# X13-Backplane.net
KiCad netlist of a schematic drawn in EAGLE
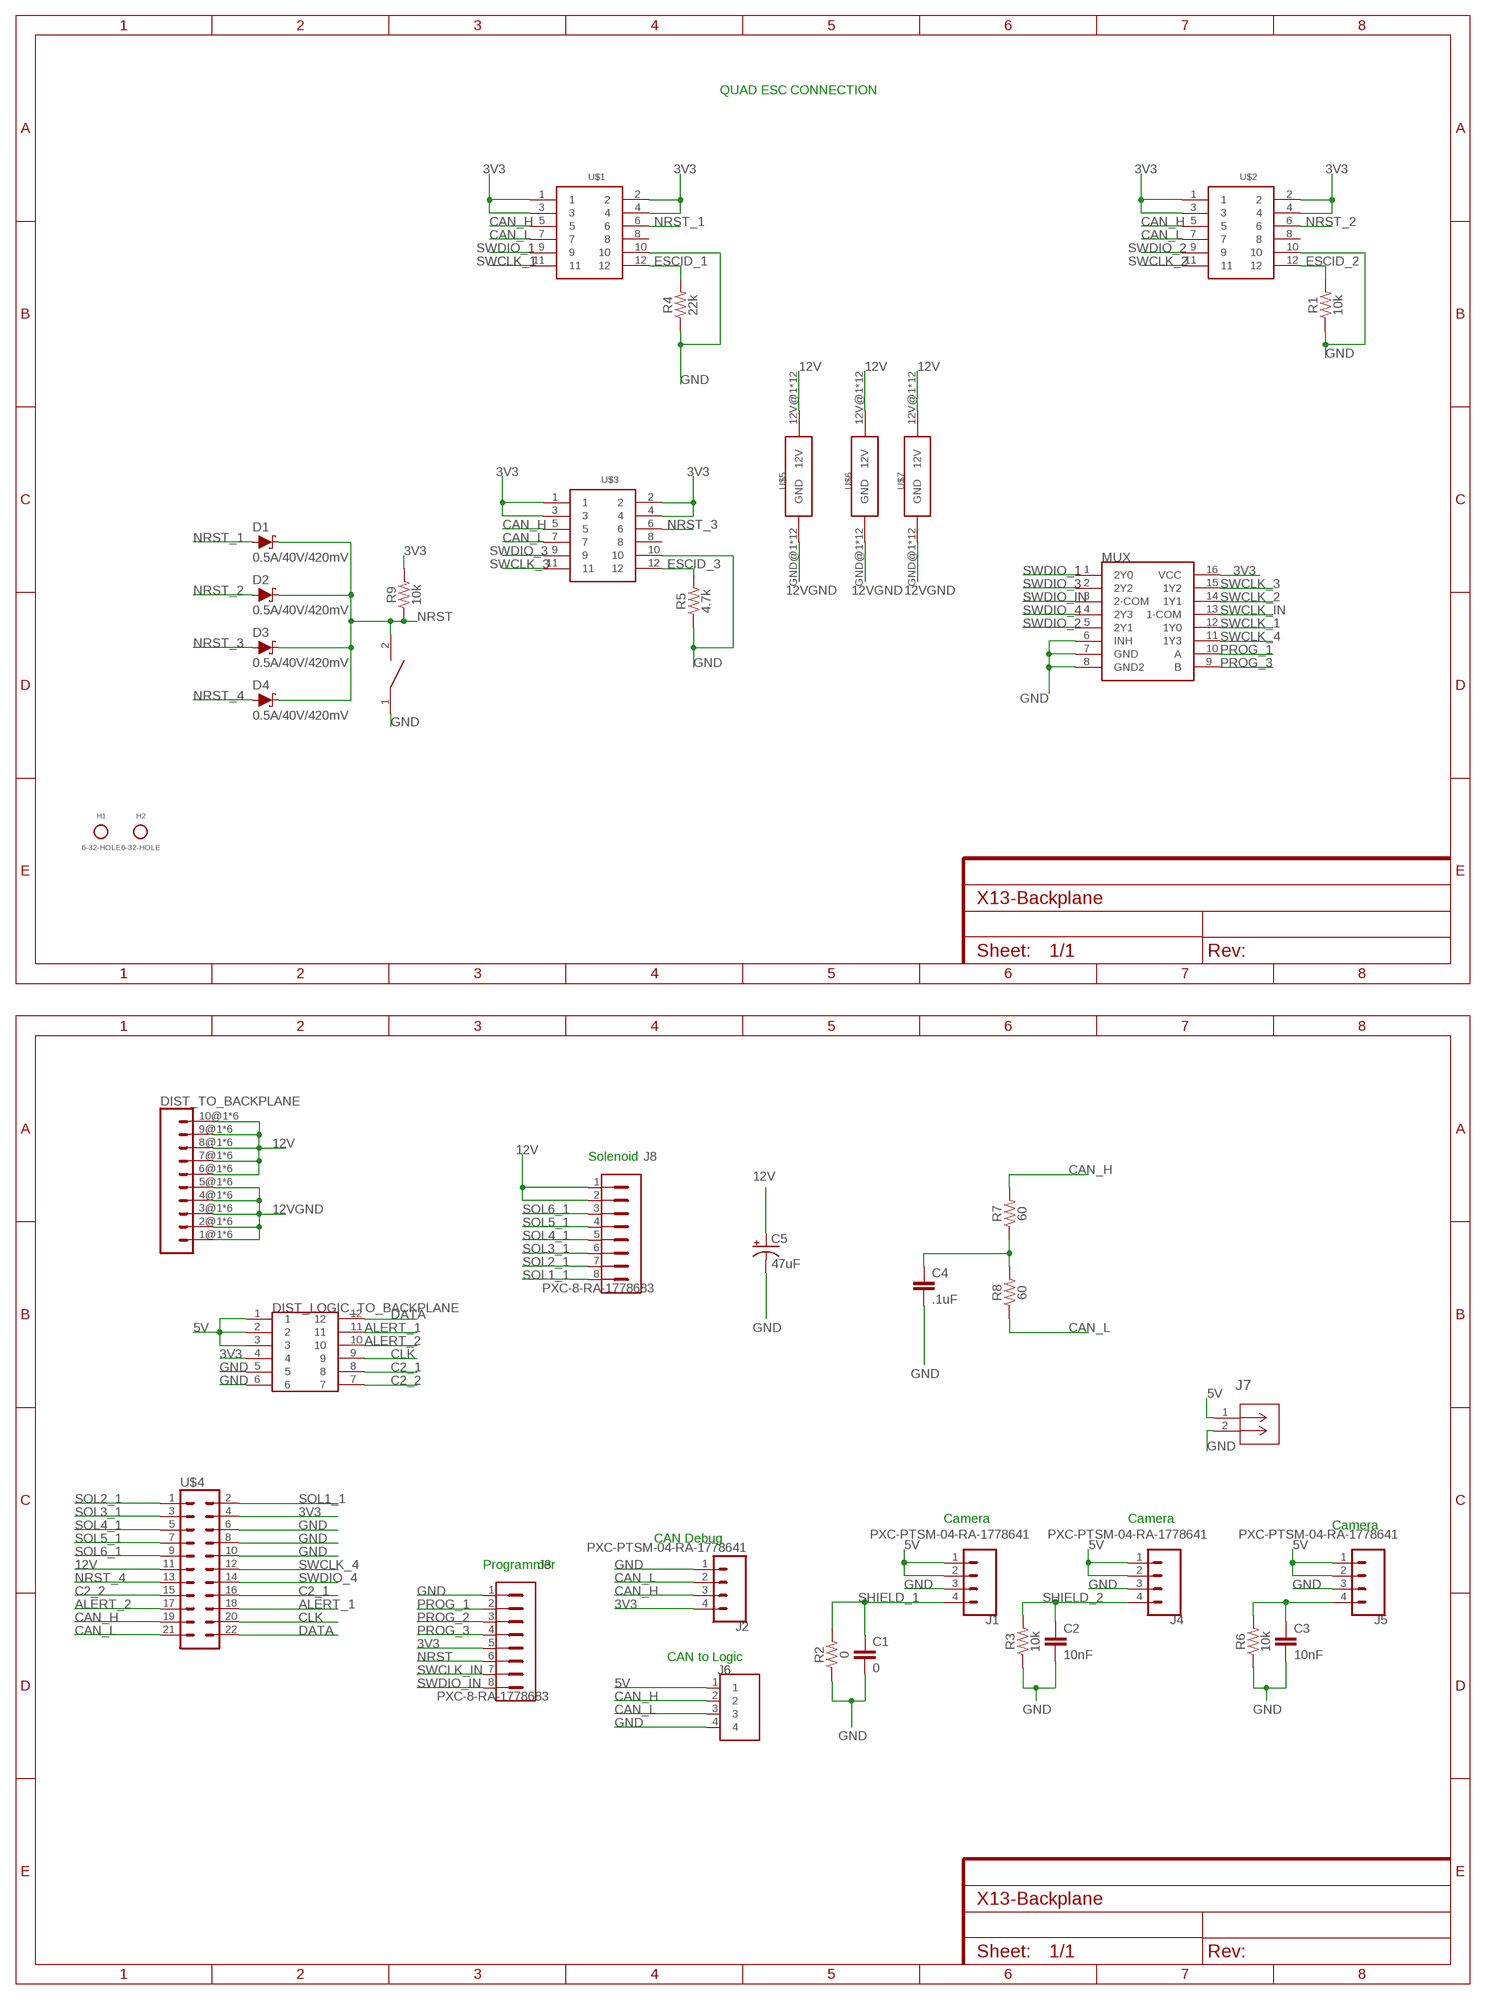
[diagram p0: schematic, sheet 1]

(export (version "E")
  (design (tool "Eeschema 10.0.6"))
  (components
    (comp (ref "C1")
      (value "0")
      (footprint "eagle-import:0603")
      (libsource (lib "eagle-import") (part "10NF-0603-50V-10%"))
    )
    (comp (ref "C2")
      (value "10nF")
      (footprint "eagle-import:0603")
      (libsource (lib "eagle-import") (part "10NF-0603-50V-10%"))
    )
    (comp (ref "C3")
      (value "10nF")
      (footprint "eagle-import:0603")
      (libsource (lib "eagle-import") (part "10NF-0603-50V-10%"))
    )
    (comp (ref "C4")
      (value ".1uF")
      (footprint "eagle-import:0603")
      (libsource (lib "eagle-import") (part "10NF-0603-50V-10%"))
    )
    (comp (ref "C5")
      (value "47uF")
      (footprint "eagle-import:PANASONIC_D")
      (libsource (lib "eagle-import") (part "47UF-POLAR-PANASONIC_D-35V-20%"))
    )
    (comp (ref "D1")
      (value "0.5A/40V/420mV")
      (footprint "eagle-import:SOD-323")
      (libsource (lib "eagle-import") (part "DIODE-SCHOTTKY-PMEG4005EJ"))
    )
    (comp (ref "D2")
      (value "0.5A/40V/420mV")
      (footprint "eagle-import:SOD-323")
      (libsource (lib "eagle-import") (part "DIODE-SCHOTTKY-PMEG4005EJ"))
    )
    (comp (ref "D3")
      (value "0.5A/40V/420mV")
      (footprint "eagle-import:SOD-323")
      (libsource (lib "eagle-import") (part "DIODE-SCHOTTKY-PMEG4005EJ"))
    )
    (comp (ref "D4")
      (value "0.5A/40V/420mV")
      (footprint "eagle-import:SOD-323")
      (libsource (lib "eagle-import") (part "DIODE-SCHOTTKY-PMEG4005EJ"))
    )
    (comp (ref "DIST_LOGIC_TO_BACKPLANE")
      (value "IPL1-106-01-L-D-K")
      (footprint "eagle-import:IPL1-106-01-L-D-K")
      (libsource (lib "eagle-import") (part "IPL1-106-01-L-D-K"))
    )
    (comp (ref "DIST_TO_BACKPLANE")
      (value "MPPT-10-01-01-L-RA-SD")
      (footprint "eagle-import:MPPT-10-01-01-L-RA-SD")
      (libsource (lib "eagle-import") (part "MPPT-10-01-01-L-RA-SD"))
    )
    (comp (ref "H1")
      (value "6-32-HOLE")
      (footprint "eagle-import:6-32-HOLE")
      (libsource (lib "eagle-import") (part "6-32-HOLE"))
    )
    (comp (ref "H2")
      (value "6-32-HOLE")
      (footprint "eagle-import:6-32-HOLE")
      (libsource (lib "eagle-import") (part "6-32-HOLE"))
    )
    (comp (ref "J1")
      (value "PXC-PTSM-04-RA-1778641")
      (footprint "eagle-import:PXC-PTSM-04-RA-1778641")
      (libsource (lib "eagle-import") (part "PXC-PTSM-04-RA-1778641"))
    )
    (comp (ref "J2")
      (value "PXC-PTSM-04-RA-1778641")
      (footprint "eagle-import:PXC-PTSM-04-RA-1778641")
      (libsource (lib "eagle-import") (part "PXC-PTSM-04-RA-1778641"))
    )
    (comp (ref "J3")
      (value "PXC-8-RA-1778683")
      (footprint "eagle-import:PXC-8-RA-1778683")
      (libsource (lib "eagle-import") (part "PXC-8-RA-1778683"))
    )
    (comp (ref "J4")
      (value "PXC-PTSM-04-RA-1778641")
      (footprint "eagle-import:PXC-PTSM-04-RA-1778641")
      (libsource (lib "eagle-import") (part "PXC-PTSM-04-RA-1778641"))
    )
    (comp (ref "J5")
      (value "PXC-PTSM-04-RA-1778641")
      (footprint "eagle-import:PXC-PTSM-04-RA-1778641")
      (libsource (lib "eagle-import") (part "PXC-PTSM-04-RA-1778641"))
    )
    (comp (ref "J6")
      (value "284512-4")
      (footprint "eagle-import:TE_284512-4")
      (fields (field (name "MANUFACTURER") "TE"))
      (libsource (lib "eagle-import") (part "284512-4"))
    )
    (comp (ref "J7")
      (value "POE_TERMINAL")
      (footprint "eagle-import:CONN2_282834-2_TEC")
      (fields
        (field (name "MANUFACTURER_PART_NUMBER") "282834-2")
        (field (name "COPYRIGHT") "Copyright (C) 2016 Accelerated Designs. All rights reserved")
      )
      (libsource (lib "eagle-import") (part "POE_TERMINAL"))
    )
    (comp (ref "J8")
      (value "PXC-8-RA-1778683")
      (footprint "eagle-import:PXC-8-RA-1778683")
      (libsource (lib "eagle-import") (part "PXC-8-RA-1778683"))
    )
    (comp (ref "MUX")
      (value "TI-SN74LV4052A")
      (footprint "eagle-import:SOIC-16")
      (libsource (lib "eagle-import") (part "TI-SN74LV4052A"))
    )
    (comp (ref "R1")
      (value "10k")
      (footprint "eagle-import:0603")
      (libsource (lib "eagle-import") (part "10KOHM-0603-1/10W-1%"))
    )
    (comp (ref "R2")
      (value "0")
      (footprint "eagle-import:0603")
      (libsource (lib "eagle-import") (part "10KOHM-0603-1/10W-1%"))
    )
    (comp (ref "R3")
      (value "10k")
      (footprint "eagle-import:0603")
      (libsource (lib "eagle-import") (part "10KOHM-0603-1/10W-1%"))
    )
    (comp (ref "R4")
      (value "22k")
      (footprint "eagle-import:0603")
      (libsource (lib "eagle-import") (part "26.7KOHM0603-1/10W-1%"))
    )
    (comp (ref "R5")
      (value "4.7k")
      (footprint "eagle-import:0603")
      (libsource (lib "eagle-import") (part "1KOHM-0603-1/10W-1%"))
    )
    (comp (ref "R6")
      (value "10k")
      (footprint "eagle-import:0603")
      (libsource (lib "eagle-import") (part "10KOHM-0603-1/10W-1%"))
    )
    (comp (ref "R7")
      (value "60")
      (footprint "eagle-import:0603")
      (libsource (lib "eagle-import") (part "68.1KOHM-0603-1/10W-1%"))
    )
    (comp (ref "R8")
      (value "60")
      (footprint "eagle-import:0603")
      (libsource (lib "eagle-import") (part "68.1KOHM-0603-1/10W-1%"))
    )
    (comp (ref "R9")
      (value "10k")
      (footprint "eagle-import:0603")
      (libsource (lib "eagle-import") (part "10KOHM-0603-1/10W-1%"))
    )
    (comp (ref "U$1")
      (value "BACKPLANE_CONNECTORSBKP")
      (footprint "eagle-import:BACKPLANE_CONNECTORS_BKP")
      (libsource (lib "eagle-import") (part "BACKPLANE_CONNECTORSBKP"))
    )
    (comp (ref "U$2")
      (value "BACKPLANE_CONNECTORSBKP")
      (footprint "eagle-import:BACKPLANE_CONNECTORS_BKP")
      (libsource (lib "eagle-import") (part "BACKPLANE_CONNECTORSBKP"))
    )
    (comp (ref "U$3")
      (value "BACKPLANE_CONNECTORSBKP")
      (footprint "eagle-import:BACKPLANE_CONNECTORS_BKP")
      (libsource (lib "eagle-import") (part "BACKPLANE_CONNECTORSBKP"))
    )
    (comp (ref "U$4")
      (value "BKP-TO-SOL")
      (footprint "eagle-import:BKP-TO-SOL_TMM-111-01-T-D")
      (libsource (lib "eagle-import") (part "BKP-TO-SOL"))
    )
    (comp (ref "U$5")
      (value "BACKPLANE_ESC_ADAPTER_PWRBKP")
      (footprint "eagle-import:BACKPLANE_ESC_ADAPTER_BKP_PWR")
      (libsource (lib "eagle-import") (part "BACKPLANE_ESC_ADAPTER_PWRBKP"))
    )
    (comp (ref "U$6")
      (value "BACKPLANE_ESC_ADAPTER_PWRBKP")
      (footprint "eagle-import:BACKPLANE_ESC_ADAPTER_BKP_PWR")
      (libsource (lib "eagle-import") (part "BACKPLANE_ESC_ADAPTER_PWRBKP"))
    )
    (comp (ref "U$7")
      (value "BACKPLANE_ESC_ADAPTER_PWRBKP")
      (footprint "eagle-import:BACKPLANE_ESC_ADAPTER_BKP_PWR")
      (libsource (lib "eagle-import") (part "BACKPLANE_ESC_ADAPTER_PWRBKP"))
    )
    (comp (ref "U$8")
      (value "DISCRETECOMPONENTS_SWITCH")
      (footprint "eagle-import:DISCRETECOMPONENTS_SW_2512")
      (libsource (lib "eagle-import") (part "DISCRETECOMPONENTS_SWITCH"))
    )
  )
  (nets
    (net (code "1") (name "/3V3") (class "Default")
      (node (ref "DIST_LOGIC_TO_BACKPLANE") (pin "4") (pinfunction "4_4") (pintype "bidirectional"))
      (node (ref "J2") (pin "4") (pinfunction "4_4") (pintype "passive"))
      (node (ref "J3") (pin "5") (pinfunction "5_5") (pintype "passive"))
      (node (ref "MUX") (pin "16") (pinfunction "VCC_16") (pintype "bidirectional"))
      (node (ref "R9") (pin "2") (pinfunction "2_2") (pintype "passive"))
      (node (ref "U$1") (pin "1") (pinfunction "1_1") (pintype "passive"))
      (node (ref "U$1") (pin "2") (pinfunction "2_2") (pintype "passive"))
      (node (ref "U$1") (pin "3") (pinfunction "3_3") (pintype "passive"))
      (node (ref "U$1") (pin "4") (pinfunction "4_4") (pintype "passive"))
      (node (ref "U$2") (pin "1") (pinfunction "1_1") (pintype "passive"))
      (node (ref "U$2") (pin "2") (pinfunction "2_2") (pintype "passive"))
      (node (ref "U$2") (pin "3") (pinfunction "3_3") (pintype "passive"))
      (node (ref "U$2") (pin "4") (pinfunction "4_4") (pintype "passive"))
      (node (ref "U$3") (pin "1") (pinfunction "1_1") (pintype "passive"))
      (node (ref "U$3") (pin "2") (pinfunction "2_2") (pintype "passive"))
      (node (ref "U$3") (pin "3") (pinfunction "3_3") (pintype "passive"))
      (node (ref "U$3") (pin "4") (pinfunction "4_4") (pintype "passive"))
      (node (ref "U$4") (pin "4") (pinfunction "4_4") (pintype "passive"))
    )
    (net (code "2") (name "/5V") (class "Default")
      (node (ref "DIST_LOGIC_TO_BACKPLANE") (pin "1") (pinfunction "1_1") (pintype "bidirectional"))
      (node (ref "DIST_LOGIC_TO_BACKPLANE") (pin "2") (pinfunction "2_2") (pintype "bidirectional"))
      (node (ref "DIST_LOGIC_TO_BACKPLANE") (pin "3") (pinfunction "3_3") (pintype "bidirectional"))
      (node (ref "J1") (pin "1") (pinfunction "1_1") (pintype "passive"))
      (node (ref "J1") (pin "2") (pinfunction "2_2") (pintype "passive"))
      (node (ref "J4") (pin "1") (pinfunction "1_1") (pintype "passive"))
      (node (ref "J4") (pin "2") (pinfunction "2_2") (pintype "passive"))
      (node (ref "J5") (pin "1") (pinfunction "1_1") (pintype "passive"))
      (node (ref "J5") (pin "2") (pinfunction "2_2") (pintype "passive"))
      (node (ref "J6") (pin "1") (pinfunction "1_1") (pintype "passive"))
      (node (ref "J7") (pin "1") (pinfunction "1_1") (pintype "passive"))
    )
    (net (code "3") (name "/12V") (class "Default")
      (node (ref "C5") (pin "+") (pinfunction "+_+") (pintype "passive"))
      (node (ref "DIST_TO_BACKPLANE") (pin "10@1") (pinfunction "10_10@1") (pintype "passive"))
      (node (ref "DIST_TO_BACKPLANE") (pin "10@2") (pinfunction "10_10@2") (pintype "passive"))
      (node (ref "DIST_TO_BACKPLANE") (pin "10@3") (pinfunction "10_10@3") (pintype "passive"))
      (node (ref "DIST_TO_BACKPLANE") (pin "10@4") (pinfunction "10_10@4") (pintype "passive"))
      (node (ref "DIST_TO_BACKPLANE") (pin "10@5") (pinfunction "10_10@5") (pintype "passive"))
      (node (ref "DIST_TO_BACKPLANE") (pin "10@6") (pinfunction "10_10@6") (pintype "passive"))
      (node (ref "DIST_TO_BACKPLANE") (pin "6@1") (pinfunction "6_6@1") (pintype "passive"))
      (node (ref "DIST_TO_BACKPLANE") (pin "6@2") (pinfunction "6_6@2") (pintype "passive"))
      (node (ref "DIST_TO_BACKPLANE") (pin "6@3") (pinfunction "6_6@3") (pintype "passive"))
      (node (ref "DIST_TO_BACKPLANE") (pin "6@4") (pinfunction "6_6@4") (pintype "passive"))
      (node (ref "DIST_TO_BACKPLANE") (pin "6@5") (pinfunction "6_6@5") (pintype "passive"))
      (node (ref "DIST_TO_BACKPLANE") (pin "6@6") (pinfunction "6_6@6") (pintype "passive"))
      (node (ref "DIST_TO_BACKPLANE") (pin "7@1") (pinfunction "7_7@1") (pintype "passive"))
      (node (ref "DIST_TO_BACKPLANE") (pin "7@2") (pinfunction "7_7@2") (pintype "passive"))
      (node (ref "DIST_TO_BACKPLANE") (pin "7@3") (pinfunction "7_7@3") (pintype "passive"))
      (node (ref "DIST_TO_BACKPLANE") (pin "7@4") (pinfunction "7_7@4") (pintype "passive"))
      (node (ref "DIST_TO_BACKPLANE") (pin "7@5") (pinfunction "7_7@5") (pintype "passive"))
      (node (ref "DIST_TO_BACKPLANE") (pin "7@6") (pinfunction "7_7@6") (pintype "passive"))
      (node (ref "DIST_TO_BACKPLANE") (pin "8@1") (pinfunction "8_8@1") (pintype "passive"))
      (node (ref "DIST_TO_BACKPLANE") (pin "8@2") (pinfunction "8_8@2") (pintype "passive"))
      (node (ref "DIST_TO_BACKPLANE") (pin "8@3") (pinfunction "8_8@3") (pintype "passive"))
      (node (ref "DIST_TO_BACKPLANE") (pin "8@4") (pinfunction "8_8@4") (pintype "passive"))
      (node (ref "DIST_TO_BACKPLANE") (pin "8@5") (pinfunction "8_8@5") (pintype "passive"))
      (node (ref "DIST_TO_BACKPLANE") (pin "8@6") (pinfunction "8_8@6") (pintype "passive"))
      (node (ref "DIST_TO_BACKPLANE") (pin "9@1") (pinfunction "9_9@1") (pintype "passive"))
      (node (ref "DIST_TO_BACKPLANE") (pin "9@2") (pinfunction "9_9@2") (pintype "passive"))
      (node (ref "DIST_TO_BACKPLANE") (pin "9@3") (pinfunction "9_9@3") (pintype "passive"))
      (node (ref "DIST_TO_BACKPLANE") (pin "9@4") (pinfunction "9_9@4") (pintype "passive"))
      (node (ref "DIST_TO_BACKPLANE") (pin "9@5") (pinfunction "9_9@5") (pintype "passive"))
      (node (ref "DIST_TO_BACKPLANE") (pin "9@6") (pinfunction "9_9@6") (pintype "passive"))
      (node (ref "J8") (pin "1") (pinfunction "1_1") (pintype "passive"))
      (node (ref "J8") (pin "2") (pinfunction "2_2") (pintype "passive"))
      (node (ref "U$4") (pin "11") (pinfunction "11_11") (pintype "passive"))
      (node (ref "U$5") (pin "12V@1") (pinfunction "12V_12V@1") (pintype "bidirectional"))
      (node (ref "U$5") (pin "12V@10") (pinfunction "12V_12V@10") (pintype "bidirectional"))
      (node (ref "U$5") (pin "12V@11") (pinfunction "12V_12V@11") (pintype "bidirectional"))
      (node (ref "U$5") (pin "12V@12") (pinfunction "12V_12V@12") (pintype "bidirectional"))
      (node (ref "U$5") (pin "12V@2") (pinfunction "12V_12V@2") (pintype "bidirectional"))
      (node (ref "U$5") (pin "12V@3") (pinfunction "12V_12V@3") (pintype "bidirectional"))
      (node (ref "U$5") (pin "12V@4") (pinfunction "12V_12V@4") (pintype "bidirectional"))
      (node (ref "U$5") (pin "12V@5") (pinfunction "12V_12V@5") (pintype "bidirectional"))
      (node (ref "U$5") (pin "12V@6") (pinfunction "12V_12V@6") (pintype "bidirectional"))
      (node (ref "U$5") (pin "12V@7") (pinfunction "12V_12V@7") (pintype "bidirectional"))
      (node (ref "U$5") (pin "12V@8") (pinfunction "12V_12V@8") (pintype "bidirectional"))
      (node (ref "U$5") (pin "12V@9") (pinfunction "12V_12V@9") (pintype "bidirectional"))
      (node (ref "U$6") (pin "12V@1") (pinfunction "12V_12V@1") (pintype "bidirectional"))
      (node (ref "U$6") (pin "12V@10") (pinfunction "12V_12V@10") (pintype "bidirectional"))
      (node (ref "U$6") (pin "12V@11") (pinfunction "12V_12V@11") (pintype "bidirectional"))
      (node (ref "U$6") (pin "12V@12") (pinfunction "12V_12V@12") (pintype "bidirectional"))
      (node (ref "U$6") (pin "12V@2") (pinfunction "12V_12V@2") (pintype "bidirectional"))
      (node (ref "U$6") (pin "12V@3") (pinfunction "12V_12V@3") (pintype "bidirectional"))
      (node (ref "U$6") (pin "12V@4") (pinfunction "12V_12V@4") (pintype "bidirectional"))
      (node (ref "U$6") (pin "12V@5") (pinfunction "12V_12V@5") (pintype "bidirectional"))
      (node (ref "U$6") (pin "12V@6") (pinfunction "12V_12V@6") (pintype "bidirectional"))
      (node (ref "U$6") (pin "12V@7") (pinfunction "12V_12V@7") (pintype "bidirectional"))
      (node (ref "U$6") (pin "12V@8") (pinfunction "12V_12V@8") (pintype "bidirectional"))
      (node (ref "U$6") (pin "12V@9") (pinfunction "12V_12V@9") (pintype "bidirectional"))
      (node (ref "U$7") (pin "12V@1") (pinfunction "12V_12V@1") (pintype "bidirectional"))
      (node (ref "U$7") (pin "12V@10") (pinfunction "12V_12V@10") (pintype "bidirectional"))
      (node (ref "U$7") (pin "12V@11") (pinfunction "12V_12V@11") (pintype "bidirectional"))
      (node (ref "U$7") (pin "12V@12") (pinfunction "12V_12V@12") (pintype "bidirectional"))
      (node (ref "U$7") (pin "12V@2") (pinfunction "12V_12V@2") (pintype "bidirectional"))
      (node (ref "U$7") (pin "12V@3") (pinfunction "12V_12V@3") (pintype "bidirectional"))
      (node (ref "U$7") (pin "12V@4") (pinfunction "12V_12V@4") (pintype "bidirectional"))
      (node (ref "U$7") (pin "12V@5") (pinfunction "12V_12V@5") (pintype "bidirectional"))
      (node (ref "U$7") (pin "12V@6") (pinfunction "12V_12V@6") (pintype "bidirectional"))
      (node (ref "U$7") (pin "12V@7") (pinfunction "12V_12V@7") (pintype "bidirectional"))
      (node (ref "U$7") (pin "12V@8") (pinfunction "12V_12V@8") (pintype "bidirectional"))
      (node (ref "U$7") (pin "12V@9") (pinfunction "12V_12V@9") (pintype "bidirectional"))
    )
    (net (code "4") (name "/12VGND") (class "Default")
      (node (ref "DIST_TO_BACKPLANE") (pin "1@1") (pinfunction "1_1@1") (pintype "passive"))
      (node (ref "DIST_TO_BACKPLANE") (pin "1@2") (pinfunction "1_1@2") (pintype "passive"))
      (node (ref "DIST_TO_BACKPLANE") (pin "1@3") (pinfunction "1_1@3") (pintype "passive"))
      (node (ref "DIST_TO_BACKPLANE") (pin "1@4") (pinfunction "1_1@4") (pintype "passive"))
      (node (ref "DIST_TO_BACKPLANE") (pin "1@5") (pinfunction "1_1@5") (pintype "passive"))
      (node (ref "DIST_TO_BACKPLANE") (pin "1@6") (pinfunction "1_1@6") (pintype "passive"))
      (node (ref "DIST_TO_BACKPLANE") (pin "2@1") (pinfunction "2_2@1") (pintype "passive"))
      (node (ref "DIST_TO_BACKPLANE") (pin "2@2") (pinfunction "2_2@2") (pintype "passive"))
      (node (ref "DIST_TO_BACKPLANE") (pin "2@3") (pinfunction "2_2@3") (pintype "passive"))
      (node (ref "DIST_TO_BACKPLANE") (pin "2@4") (pinfunction "2_2@4") (pintype "passive"))
      (node (ref "DIST_TO_BACKPLANE") (pin "2@5") (pinfunction "2_2@5") (pintype "passive"))
      (node (ref "DIST_TO_BACKPLANE") (pin "2@6") (pinfunction "2_2@6") (pintype "passive"))
      (node (ref "DIST_TO_BACKPLANE") (pin "3@1") (pinfunction "3_3@1") (pintype "passive"))
      (node (ref "DIST_TO_BACKPLANE") (pin "3@2") (pinfunction "3_3@2") (pintype "passive"))
      (node (ref "DIST_TO_BACKPLANE") (pin "3@3") (pinfunction "3_3@3") (pintype "passive"))
      (node (ref "DIST_TO_BACKPLANE") (pin "3@4") (pinfunction "3_3@4") (pintype "passive"))
      (node (ref "DIST_TO_BACKPLANE") (pin "3@5") (pinfunction "3_3@5") (pintype "passive"))
      (node (ref "DIST_TO_BACKPLANE") (pin "3@6") (pinfunction "3_3@6") (pintype "passive"))
      (node (ref "DIST_TO_BACKPLANE") (pin "4@1") (pinfunction "4_4@1") (pintype "passive"))
      (node (ref "DIST_TO_BACKPLANE") (pin "4@2") (pinfunction "4_4@2") (pintype "passive"))
      (node (ref "DIST_TO_BACKPLANE") (pin "4@3") (pinfunction "4_4@3") (pintype "passive"))
      (node (ref "DIST_TO_BACKPLANE") (pin "4@4") (pinfunction "4_4@4") (pintype "passive"))
      (node (ref "DIST_TO_BACKPLANE") (pin "4@5") (pinfunction "4_4@5") (pintype "passive"))
      (node (ref "DIST_TO_BACKPLANE") (pin "4@6") (pinfunction "4_4@6") (pintype "passive"))
      (node (ref "DIST_TO_BACKPLANE") (pin "5@1") (pinfunction "5_5@1") (pintype "passive"))
      (node (ref "DIST_TO_BACKPLANE") (pin "5@2") (pinfunction "5_5@2") (pintype "passive"))
      (node (ref "DIST_TO_BACKPLANE") (pin "5@3") (pinfunction "5_5@3") (pintype "passive"))
      (node (ref "DIST_TO_BACKPLANE") (pin "5@4") (pinfunction "5_5@4") (pintype "passive"))
      (node (ref "DIST_TO_BACKPLANE") (pin "5@5") (pinfunction "5_5@5") (pintype "passive"))
      (node (ref "DIST_TO_BACKPLANE") (pin "5@6") (pinfunction "5_5@6") (pintype "passive"))
      (node (ref "U$5") (pin "GND@1") (pinfunction "GND_GND@1") (pintype "bidirectional"))
      (node (ref "U$5") (pin "GND@10") (pinfunction "GND_GND@10") (pintype "bidirectional"))
      (node (ref "U$5") (pin "GND@11") (pinfunction "GND_GND@11") (pintype "bidirectional"))
      (node (ref "U$5") (pin "GND@12") (pinfunction "GND_GND@12") (pintype "bidirectional"))
      (node (ref "U$5") (pin "GND@2") (pinfunction "GND_GND@2") (pintype "bidirectional"))
      (node (ref "U$5") (pin "GND@3") (pinfunction "GND_GND@3") (pintype "bidirectional"))
      (node (ref "U$5") (pin "GND@4") (pinfunction "GND_GND@4") (pintype "bidirectional"))
      (node (ref "U$5") (pin "GND@5") (pinfunction "GND_GND@5") (pintype "bidirectional"))
      (node (ref "U$5") (pin "GND@6") (pinfunction "GND_GND@6") (pintype "bidirectional"))
      (node (ref "U$5") (pin "GND@7") (pinfunction "GND_GND@7") (pintype "bidirectional"))
      (node (ref "U$5") (pin "GND@8") (pinfunction "GND_GND@8") (pintype "bidirectional"))
      (node (ref "U$5") (pin "GND@9") (pinfunction "GND_GND@9") (pintype "bidirectional"))
      (node (ref "U$6") (pin "GND@1") (pinfunction "GND_GND@1") (pintype "bidirectional"))
      (node (ref "U$6") (pin "GND@10") (pinfunction "GND_GND@10") (pintype "bidirectional"))
      (node (ref "U$6") (pin "GND@11") (pinfunction "GND_GND@11") (pintype "bidirectional"))
      (node (ref "U$6") (pin "GND@12") (pinfunction "GND_GND@12") (pintype "bidirectional"))
      (node (ref "U$6") (pin "GND@2") (pinfunction "GND_GND@2") (pintype "bidirectional"))
      (node (ref "U$6") (pin "GND@3") (pinfunction "GND_GND@3") (pintype "bidirectional"))
      (node (ref "U$6") (pin "GND@4") (pinfunction "GND_GND@4") (pintype "bidirectional"))
      (node (ref "U$6") (pin "GND@5") (pinfunction "GND_GND@5") (pintype "bidirectional"))
      (node (ref "U$6") (pin "GND@6") (pinfunction "GND_GND@6") (pintype "bidirectional"))
      (node (ref "U$6") (pin "GND@7") (pinfunction "GND_GND@7") (pintype "bidirectional"))
      (node (ref "U$6") (pin "GND@8") (pinfunction "GND_GND@8") (pintype "bidirectional"))
      (node (ref "U$6") (pin "GND@9") (pinfunction "GND_GND@9") (pintype "bidirectional"))
      (node (ref "U$7") (pin "GND@1") (pinfunction "GND_GND@1") (pintype "bidirectional"))
      (node (ref "U$7") (pin "GND@10") (pinfunction "GND_GND@10") (pintype "bidirectional"))
      (node (ref "U$7") (pin "GND@11") (pinfunction "GND_GND@11") (pintype "bidirectional"))
      (node (ref "U$7") (pin "GND@12") (pinfunction "GND_GND@12") (pintype "bidirectional"))
      (node (ref "U$7") (pin "GND@2") (pinfunction "GND_GND@2") (pintype "bidirectional"))
      (node (ref "U$7") (pin "GND@3") (pinfunction "GND_GND@3") (pintype "bidirectional"))
      (node (ref "U$7") (pin "GND@4") (pinfunction "GND_GND@4") (pintype "bidirectional"))
      (node (ref "U$7") (pin "GND@5") (pinfunction "GND_GND@5") (pintype "bidirectional"))
      (node (ref "U$7") (pin "GND@6") (pinfunction "GND_GND@6") (pintype "bidirectional"))
      (node (ref "U$7") (pin "GND@7") (pinfunction "GND_GND@7") (pintype "bidirectional"))
      (node (ref "U$7") (pin "GND@8") (pinfunction "GND_GND@8") (pintype "bidirectional"))
      (node (ref "U$7") (pin "GND@9") (pinfunction "GND_GND@9") (pintype "bidirectional"))
    )
    (net (code "5") (name "/ALERT_1") (class "Default")
      (node (ref "DIST_LOGIC_TO_BACKPLANE") (pin "11") (pinfunction "11_11") (pintype "bidirectional"))
      (node (ref "U$4") (pin "18") (pinfunction "18_18") (pintype "passive"))
    )
    (net (code "6") (name "/ALERT_2") (class "Default")
      (node (ref "DIST_LOGIC_TO_BACKPLANE") (pin "10") (pinfunction "10_10") (pintype "bidirectional"))
      (node (ref "U$4") (pin "17") (pinfunction "17_17") (pintype "passive"))
    )
    (net (code "7") (name "/C2_1") (class "Default")
      (node (ref "DIST_LOGIC_TO_BACKPLANE") (pin "8") (pinfunction "8_8") (pintype "bidirectional"))
      (node (ref "U$4") (pin "16") (pinfunction "16_16") (pintype "passive"))
    )
    (net (code "8") (name "/C2_2") (class "Default")
      (node (ref "DIST_LOGIC_TO_BACKPLANE") (pin "7") (pinfunction "7_7") (pintype "bidirectional"))
      (node (ref "U$4") (pin "15") (pinfunction "15_15") (pintype "passive"))
    )
    (net (code "9") (name "/CAN_H") (class "Default")
      (node (ref "J2") (pin "3") (pinfunction "3_3") (pintype "passive"))
      (node (ref "J6") (pin "2") (pinfunction "2_2") (pintype "passive"))
      (node (ref "R7") (pin "2") (pinfunction "2_2") (pintype "passive"))
      (node (ref "U$1") (pin "5") (pinfunction "5_5") (pintype "passive"))
      (node (ref "U$2") (pin "5") (pinfunction "5_5") (pintype "passive"))
      (node (ref "U$3") (pin "5") (pinfunction "5_5") (pintype "passive"))
      (node (ref "U$4") (pin "19") (pinfunction "19_19") (pintype "passive"))
    )
    (net (code "10") (name "/CAN_L") (class "Default")
      (node (ref "J2") (pin "2") (pinfunction "2_2") (pintype "passive"))
      (node (ref "J6") (pin "3") (pinfunction "3_3") (pintype "passive"))
      (node (ref "R8") (pin "1") (pinfunction "1_1") (pintype "passive"))
      (node (ref "U$1") (pin "7") (pinfunction "7_7") (pintype "passive"))
      (node (ref "U$2") (pin "7") (pinfunction "7_7") (pintype "passive"))
      (node (ref "U$3") (pin "7") (pinfunction "7_7") (pintype "passive"))
      (node (ref "U$4") (pin "21") (pinfunction "21_21") (pintype "passive"))
    )
    (net (code "11") (name "/CLK") (class "Default")
      (node (ref "DIST_LOGIC_TO_BACKPLANE") (pin "9") (pinfunction "9_9") (pintype "bidirectional"))
      (node (ref "U$4") (pin "20") (pinfunction "20_20") (pintype "passive"))
    )
    (net (code "12") (name "/DATA") (class "Default")
      (node (ref "DIST_LOGIC_TO_BACKPLANE") (pin "12") (pinfunction "12_12") (pintype "bidirectional"))
      (node (ref "U$4") (pin "22") (pinfunction "22_22") (pintype "passive"))
    )
    (net (code "13") (name "/ESCID_1") (class "Default")
      (node (ref "R4") (pin "2") (pinfunction "2_2") (pintype "passive"))
      (node (ref "U$1") (pin "12") (pinfunction "12_12") (pintype "passive"))
    )
    (net (code "14") (name "/ESCID_2") (class "Default")
      (node (ref "R1") (pin "2") (pinfunction "2_2") (pintype "passive"))
      (node (ref "U$2") (pin "12") (pinfunction "12_12") (pintype "passive"))
    )
    (net (code "15") (name "/ESCID_3") (class "Default")
      (node (ref "R5") (pin "2") (pinfunction "2_2") (pintype "passive"))
      (node (ref "U$3") (pin "12") (pinfunction "12_12") (pintype "passive"))
    )
    (net (code "16") (name "/GND") (class "Default")
      (node (ref "C1") (pin "2") (pinfunction "2_2") (pintype "passive"))
      (node (ref "C2") (pin "2") (pinfunction "2_2") (pintype "passive"))
      (node (ref "C3") (pin "2") (pinfunction "2_2") (pintype "passive"))
      (node (ref "C4") (pin "2") (pinfunction "2_2") (pintype "passive"))
      (node (ref "C5") (pin "-") (pinfunction "-_-") (pintype "passive"))
      (node (ref "DIST_LOGIC_TO_BACKPLANE") (pin "5") (pinfunction "5_5") (pintype "bidirectional"))
      (node (ref "DIST_LOGIC_TO_BACKPLANE") (pin "6") (pinfunction "6_6") (pintype "bidirectional"))
      (node (ref "J1") (pin "3") (pinfunction "3_3") (pintype "passive"))
      (node (ref "J2") (pin "1") (pinfunction "1_1") (pintype "passive"))
      (node (ref "J3") (pin "1") (pinfunction "1_1") (pintype "passive"))
      (node (ref "J4") (pin "3") (pinfunction "3_3") (pintype "passive"))
      (node (ref "J5") (pin "3") (pinfunction "3_3") (pintype "passive"))
      (node (ref "J6") (pin "4") (pinfunction "4_4") (pintype "passive"))
      (node (ref "J7") (pin "2") (pinfunction "2_2") (pintype "passive"))
      (node (ref "MUX") (pin "6") (pinfunction "INH_6") (pintype "bidirectional"))
      (node (ref "MUX") (pin "7") (pinfunction "GND_7") (pintype "bidirectional"))
      (node (ref "MUX") (pin "8") (pinfunction "GND2_8") (pintype "bidirectional"))
      (node (ref "R1") (pin "1") (pinfunction "1_1") (pintype "passive"))
      (node (ref "R2") (pin "1") (pinfunction "1_1") (pintype "passive"))
      (node (ref "R3") (pin "1") (pinfunction "1_1") (pintype "passive"))
      (node (ref "R4") (pin "1") (pinfunction "1_1") (pintype "passive"))
      (node (ref "R5") (pin "1") (pinfunction "1_1") (pintype "passive"))
      (node (ref "R6") (pin "1") (pinfunction "1_1") (pintype "passive"))
      (node (ref "U$1") (pin "10") (pinfunction "10_10") (pintype "passive"))
      (node (ref "U$2") (pin "10") (pinfunction "10_10") (pintype "passive"))
      (node (ref "U$3") (pin "10") (pinfunction "10_10") (pintype "passive"))
      (node (ref "U$4") (pin "10") (pinfunction "10_10") (pintype "passive"))
      (node (ref "U$4") (pin "6") (pinfunction "6_6") (pintype "passive"))
      (node (ref "U$4") (pin "8") (pinfunction "8_8") (pintype "passive"))
      (node (ref "U$8") (pin "1") (pinfunction "P$1_1") (pintype "bidirectional"))
    )
    (net (code "17") (name "/NRST") (class "Default")
      (node (ref "D1") (pin "C") (pinfunction "C_C") (pintype "passive"))
      (node (ref "D2") (pin "C") (pinfunction "C_C") (pintype "passive"))
      (node (ref "D3") (pin "C") (pinfunction "C_C") (pintype "passive"))
      (node (ref "D4") (pin "C") (pinfunction "C_C") (pintype "passive"))
      (node (ref "J3") (pin "6") (pinfunction "6_6") (pintype "passive"))
      (node (ref "R9") (pin "1") (pinfunction "1_1") (pintype "passive"))
      (node (ref "U$8") (pin "2") (pinfunction "P$2_2") (pintype "bidirectional"))
    )
    (net (code "18") (name "/NRST_1") (class "Default")
      (node (ref "D1") (pin "A") (pinfunction "A_A") (pintype "passive"))
      (node (ref "U$1") (pin "6") (pinfunction "6_6") (pintype "passive"))
    )
    (net (code "19") (name "/NRST_2") (class "Default")
      (node (ref "D2") (pin "A") (pinfunction "A_A") (pintype "passive"))
      (node (ref "U$2") (pin "6") (pinfunction "6_6") (pintype "passive"))
    )
    (net (code "20") (name "/NRST_3") (class "Default")
      (node (ref "D3") (pin "A") (pinfunction "A_A") (pintype "passive"))
      (node (ref "U$3") (pin "6") (pinfunction "6_6") (pintype "passive"))
    )
    (net (code "21") (name "/NRST_4") (class "Default")
      (node (ref "D4") (pin "A") (pinfunction "A_A") (pintype "passive"))
      (node (ref "U$4") (pin "13") (pinfunction "13_13") (pintype "passive"))
    )
    (net (code "22") (name "/PROG_1") (class "Default")
      (node (ref "J3") (pin "2") (pinfunction "2_2") (pintype "passive"))
      (node (ref "MUX") (pin "10") (pinfunction "A_10") (pintype "bidirectional"))
    )
    (net (code "23") (name "/PROG_2") (class "Default")
      (node (ref "J3") (pin "3") (pinfunction "3_3") (pintype "passive"))
    )
    (net (code "24") (name "/PROG_3") (class "Default")
      (node (ref "J3") (pin "4") (pinfunction "4_4") (pintype "passive"))
      (node (ref "MUX") (pin "9") (pinfunction "B_9") (pintype "bidirectional"))
    )
    (net (code "25") (name "/SHIELD_1") (class "Default")
      (node (ref "C1") (pin "1") (pinfunction "1_1") (pintype "passive"))
      (node (ref "J1") (pin "4") (pinfunction "4_4") (pintype "passive"))
      (node (ref "R2") (pin "2") (pinfunction "2_2") (pintype "passive"))
    )
    (net (code "26") (name "/SHIELD_2") (class "Default")
      (node (ref "C2") (pin "1") (pinfunction "1_1") (pintype "passive"))
      (node (ref "J4") (pin "4") (pinfunction "4_4") (pintype "passive"))
      (node (ref "R3") (pin "2") (pinfunction "2_2") (pintype "passive"))
    )
    (net (code "27") (name "/SOL1_1") (class "Default")
      (node (ref "J8") (pin "8") (pinfunction "8_8") (pintype "passive"))
      (node (ref "U$4") (pin "2") (pinfunction "2_2") (pintype "passive"))
    )
    (net (code "28") (name "/SOL2_1") (class "Default")
      (node (ref "J8") (pin "7") (pinfunction "7_7") (pintype "passive"))
      (node (ref "U$4") (pin "1") (pinfunction "1_1") (pintype "passive"))
    )
    (net (code "29") (name "/SOL3_1") (class "Default")
      (node (ref "J8") (pin "6") (pinfunction "6_6") (pintype "passive"))
      (node (ref "U$4") (pin "3") (pinfunction "3_3") (pintype "passive"))
    )
    (net (code "30") (name "/SOL4_1") (class "Default")
      (node (ref "J8") (pin "5") (pinfunction "5_5") (pintype "passive"))
      (node (ref "U$4") (pin "5") (pinfunction "5_5") (pintype "passive"))
    )
    (net (code "31") (name "/SOL5_1") (class "Default")
      (node (ref "J8") (pin "4") (pinfunction "4_4") (pintype "passive"))
      (node (ref "U$4") (pin "7") (pinfunction "7_7") (pintype "passive"))
    )
    (net (code "32") (name "/SOL6_1") (class "Default")
      (node (ref "J8") (pin "3") (pinfunction "3_3") (pintype "passive"))
      (node (ref "U$4") (pin "9") (pinfunction "9_9") (pintype "passive"))
    )
    (net (code "33") (name "/SWCLK_1") (class "Default")
      (node (ref "MUX") (pin "12") (pinfunction "1Y0_12") (pintype "bidirectional"))
      (node (ref "U$1") (pin "11") (pinfunction "11_11") (pintype "passive"))
    )
    (net (code "34") (name "/SWCLK_2") (class "Default")
      (node (ref "MUX") (pin "14") (pinfunction "1Y1_14") (pintype "bidirectional"))
      (node (ref "U$2") (pin "11") (pinfunction "11_11") (pintype "passive"))
    )
    (net (code "35") (name "/SWCLK_3") (class "Default")
      (node (ref "MUX") (pin "15") (pinfunction "1Y2_15") (pintype "bidirectional"))
      (node (ref "U$3") (pin "11") (pinfunction "11_11") (pintype "passive"))
    )
    (net (code "36") (name "/SWCLK_4") (class "Default")
      (node (ref "MUX") (pin "11") (pinfunction "1Y3_11") (pintype "bidirectional"))
      (node (ref "U$4") (pin "12") (pinfunction "12_12") (pintype "passive"))
    )
    (net (code "37") (name "/SWCLK_IN") (class "Default")
      (node (ref "J3") (pin "7") (pinfunction "7_7") (pintype "passive"))
      (node (ref "MUX") (pin "13") (pinfunction "1-COM_13") (pintype "bidirectional"))
    )
    (net (code "38") (name "/SWDIO_1") (class "Default")
      (node (ref "MUX") (pin "1") (pinfunction "2Y0_1") (pintype "bidirectional"))
      (node (ref "U$1") (pin "9") (pinfunction "9_9") (pintype "passive"))
    )
    (net (code "39") (name "/SWDIO_2") (class "Default")
      (node (ref "MUX") (pin "5") (pinfunction "2Y1_5") (pintype "bidirectional"))
      (node (ref "U$2") (pin "9") (pinfunction "9_9") (pintype "passive"))
    )
    (net (code "40") (name "/SWDIO_3") (class "Default")
      (node (ref "MUX") (pin "2") (pinfunction "2Y2_2") (pintype "bidirectional"))
      (node (ref "U$3") (pin "9") (pinfunction "9_9") (pintype "passive"))
    )
    (net (code "41") (name "/SWDIO_4") (class "Default")
      (node (ref "MUX") (pin "4") (pinfunction "2Y3_4") (pintype "bidirectional"))
      (node (ref "U$4") (pin "14") (pinfunction "14_14") (pintype "passive"))
    )
    (net (code "42") (name "/SWDIO_IN") (class "Default")
      (node (ref "J3") (pin "8") (pinfunction "8_8") (pintype "passive"))
      (node (ref "MUX") (pin "3") (pinfunction "2-COM_3") (pintype "bidirectional"))
    )
    (net (code "43") (name "Net-(C3-Pad1)") (class "Default")
      (node (ref "C3") (pin "1") (pinfunction "1_1") (pintype "passive"))
      (node (ref "J5") (pin "4") (pinfunction "4_4") (pintype "passive"))
      (node (ref "R6") (pin "2") (pinfunction "2_2") (pintype "passive"))
    )
    (net (code "44") (name "Net-(C4-Pad1)") (class "Default")
      (node (ref "C4") (pin "1") (pinfunction "1_1") (pintype "passive"))
      (node (ref "R7") (pin "1") (pinfunction "1_1") (pintype "passive"))
      (node (ref "R8") (pin "2") (pinfunction "2_2") (pintype "passive"))
    )
    (net (code "45") (name "unconnected-(U$1-Pad8)") (class "Default")
      (node (ref "U$1") (pin "8") (pinfunction "8_8") (pintype "passive"))
    )
    (net (code "46") (name "unconnected-(U$2-Pad8)") (class "Default")
      (node (ref "U$2") (pin "8") (pinfunction "8_8") (pintype "passive"))
    )
    (net (code "47") (name "unconnected-(U$3-Pad8)") (class "Default")
      (node (ref "U$3") (pin "8") (pinfunction "8_8") (pintype "passive"))
    )
  )
)
